# backlight.net
KiCad netlist of a schematic drawn in Altium Designer
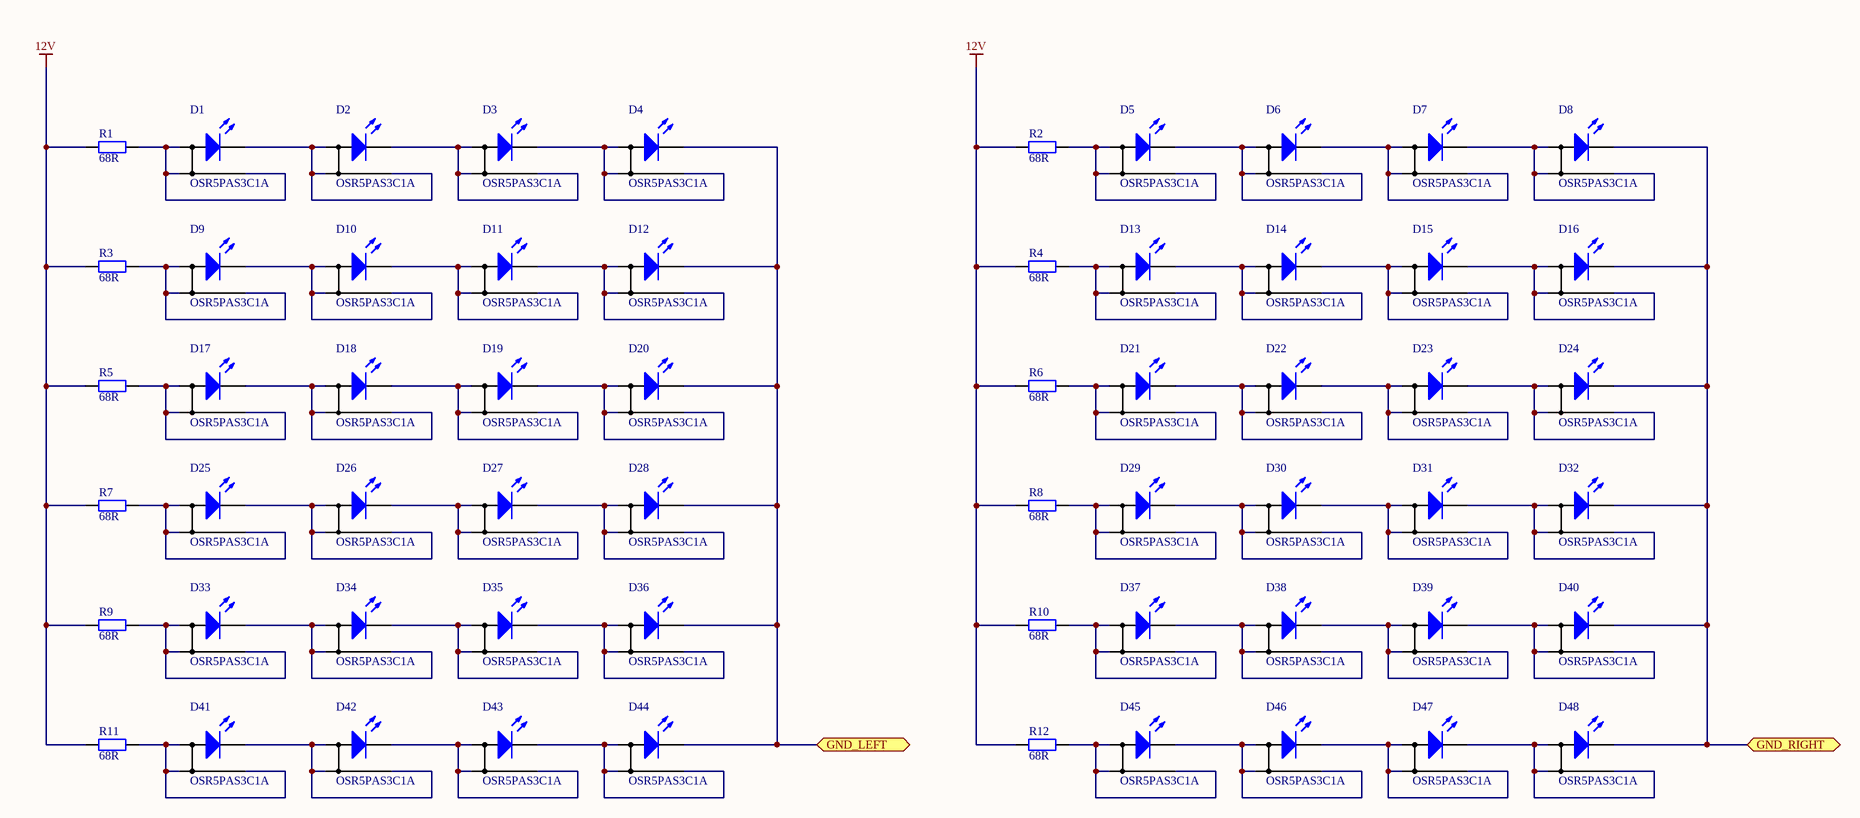
[diagram p0: backlight.SchDoc]

(export (version "E")
  (design (tool "Eeschema 10.0.6"))
  (components
    (comp (ref "D1")
      (value "DIO_LED_4pin_3528")
      (footprint "DIO_Optosupply_OSR5PAS3C1A")
      (description "High Luminous PLCC4 Power Top SMD LED")
      (fields (field (name "VALUE1") "OSR5PAS3C1A") (field (name "MANUFACTURER") "OptoSupply"))
      (libsource (lib "DSW_Lib") (part "DIO_LED_4pin_3528"))
    )
    (comp (ref "D2")
      (value "DIO_LED_4pin_3528")
      (footprint "DIO_Optosupply_OSR5PAS3C1A")
      (description "High Luminous PLCC4 Power Top SMD LED")
      (fields (field (name "VALUE1") "OSR5PAS3C1A") (field (name "MANUFACTURER") "OptoSupply"))
      (libsource (lib "DSW_Lib") (part "DIO_LED_4pin_3528"))
    )
    (comp (ref "D3")
      (value "DIO_LED_4pin_3528")
      (footprint "DIO_Optosupply_OSR5PAS3C1A")
      (description "High Luminous PLCC4 Power Top SMD LED")
      (fields (field (name "VALUE1") "OSR5PAS3C1A") (field (name "MANUFACTURER") "OptoSupply"))
      (libsource (lib "DSW_Lib") (part "DIO_LED_4pin_3528"))
    )
    (comp (ref "D4")
      (value "DIO_LED_4pin_3528")
      (footprint "DIO_Optosupply_OSR5PAS3C1A")
      (description "High Luminous PLCC4 Power Top SMD LED")
      (fields (field (name "VALUE1") "OSR5PAS3C1A") (field (name "MANUFACTURER") "OptoSupply"))
      (libsource (lib "DSW_Lib") (part "DIO_LED_4pin_3528"))
    )
    (comp (ref "D5")
      (value "DIO_LED_4pin_3528")
      (footprint "DIO_Optosupply_OSR5PAS3C1A")
      (description "High Luminous PLCC4 Power Top SMD LED")
      (fields (field (name "VALUE1") "OSR5PAS3C1A") (field (name "MANUFACTURER") "OptoSupply"))
      (libsource (lib "DSW_Lib") (part "DIO_LED_4pin_3528"))
    )
    (comp (ref "D6")
      (value "DIO_LED_4pin_3528")
      (footprint "DIO_Optosupply_OSR5PAS3C1A")
      (description "High Luminous PLCC4 Power Top SMD LED")
      (fields (field (name "VALUE1") "OSR5PAS3C1A") (field (name "MANUFACTURER") "OptoSupply"))
      (libsource (lib "DSW_Lib") (part "DIO_LED_4pin_3528"))
    )
    (comp (ref "D7")
      (value "DIO_LED_4pin_3528")
      (footprint "DIO_Optosupply_OSR5PAS3C1A")
      (description "High Luminous PLCC4 Power Top SMD LED")
      (fields (field (name "VALUE1") "OSR5PAS3C1A") (field (name "MANUFACTURER") "OptoSupply"))
      (libsource (lib "DSW_Lib") (part "DIO_LED_4pin_3528"))
    )
    (comp (ref "D8")
      (value "DIO_LED_4pin_3528")
      (footprint "DIO_Optosupply_OSR5PAS3C1A")
      (description "High Luminous PLCC4 Power Top SMD LED")
      (fields (field (name "VALUE1") "OSR5PAS3C1A") (field (name "MANUFACTURER") "OptoSupply"))
      (libsource (lib "DSW_Lib") (part "DIO_LED_4pin_3528"))
    )
    (comp (ref "D9")
      (value "DIO_LED_4pin_3528")
      (footprint "DIO_Optosupply_OSR5PAS3C1A")
      (description "High Luminous PLCC4 Power Top SMD LED")
      (fields (field (name "VALUE1") "OSR5PAS3C1A") (field (name "MANUFACTURER") "OptoSupply"))
      (libsource (lib "DSW_Lib") (part "DIO_LED_4pin_3528"))
    )
    (comp (ref "D10")
      (value "DIO_LED_4pin_3528")
      (footprint "DIO_Optosupply_OSR5PAS3C1A")
      (description "High Luminous PLCC4 Power Top SMD LED")
      (fields (field (name "VALUE1") "OSR5PAS3C1A") (field (name "MANUFACTURER") "OptoSupply"))
      (libsource (lib "DSW_Lib") (part "DIO_LED_4pin_3528"))
    )
    (comp (ref "D11")
      (value "DIO_LED_4pin_3528")
      (footprint "DIO_Optosupply_OSR5PAS3C1A")
      (description "High Luminous PLCC4 Power Top SMD LED")
      (fields (field (name "VALUE1") "OSR5PAS3C1A") (field (name "MANUFACTURER") "OptoSupply"))
      (libsource (lib "DSW_Lib") (part "DIO_LED_4pin_3528"))
    )
    (comp (ref "D12")
      (value "DIO_LED_4pin_3528")
      (footprint "DIO_Optosupply_OSR5PAS3C1A")
      (description "High Luminous PLCC4 Power Top SMD LED")
      (fields (field (name "VALUE1") "OSR5PAS3C1A") (field (name "MANUFACTURER") "OptoSupply"))
      (libsource (lib "DSW_Lib") (part "DIO_LED_4pin_3528"))
    )
    (comp (ref "D13")
      (value "DIO_LED_4pin_3528")
      (footprint "DIO_Optosupply_OSR5PAS3C1A")
      (description "High Luminous PLCC4 Power Top SMD LED")
      (fields (field (name "VALUE1") "OSR5PAS3C1A") (field (name "MANUFACTURER") "OptoSupply"))
      (libsource (lib "DSW_Lib") (part "DIO_LED_4pin_3528"))
    )
    (comp (ref "D14")
      (value "DIO_LED_4pin_3528")
      (footprint "DIO_Optosupply_OSR5PAS3C1A")
      (description "High Luminous PLCC4 Power Top SMD LED")
      (fields (field (name "VALUE1") "OSR5PAS3C1A") (field (name "MANUFACTURER") "OptoSupply"))
      (libsource (lib "DSW_Lib") (part "DIO_LED_4pin_3528"))
    )
    (comp (ref "D15")
      (value "DIO_LED_4pin_3528")
      (footprint "DIO_Optosupply_OSR5PAS3C1A")
      (description "High Luminous PLCC4 Power Top SMD LED")
      (fields (field (name "VALUE1") "OSR5PAS3C1A") (field (name "MANUFACTURER") "OptoSupply"))
      (libsource (lib "DSW_Lib") (part "DIO_LED_4pin_3528"))
    )
    (comp (ref "D16")
      (value "DIO_LED_4pin_3528")
      (footprint "DIO_Optosupply_OSR5PAS3C1A")
      (description "High Luminous PLCC4 Power Top SMD LED")
      (fields (field (name "VALUE1") "OSR5PAS3C1A") (field (name "MANUFACTURER") "OptoSupply"))
      (libsource (lib "DSW_Lib") (part "DIO_LED_4pin_3528"))
    )
    (comp (ref "D17")
      (value "DIO_LED_4pin_3528")
      (footprint "DIO_Optosupply_OSR5PAS3C1A")
      (description "High Luminous PLCC4 Power Top SMD LED")
      (fields (field (name "VALUE1") "OSR5PAS3C1A") (field (name "MANUFACTURER") "OptoSupply"))
      (libsource (lib "DSW_Lib") (part "DIO_LED_4pin_3528"))
    )
    (comp (ref "D18")
      (value "DIO_LED_4pin_3528")
      (footprint "DIO_Optosupply_OSR5PAS3C1A")
      (description "High Luminous PLCC4 Power Top SMD LED")
      (fields (field (name "VALUE1") "OSR5PAS3C1A") (field (name "MANUFACTURER") "OptoSupply"))
      (libsource (lib "DSW_Lib") (part "DIO_LED_4pin_3528"))
    )
    (comp (ref "D19")
      (value "DIO_LED_4pin_3528")
      (footprint "DIO_Optosupply_OSR5PAS3C1A")
      (description "High Luminous PLCC4 Power Top SMD LED")
      (fields (field (name "VALUE1") "OSR5PAS3C1A") (field (name "MANUFACTURER") "OptoSupply"))
      (libsource (lib "DSW_Lib") (part "DIO_LED_4pin_3528"))
    )
    (comp (ref "D20")
      (value "DIO_LED_4pin_3528")
      (footprint "DIO_Optosupply_OSR5PAS3C1A")
      (description "High Luminous PLCC4 Power Top SMD LED")
      (fields (field (name "VALUE1") "OSR5PAS3C1A") (field (name "MANUFACTURER") "OptoSupply"))
      (libsource (lib "DSW_Lib") (part "DIO_LED_4pin_3528"))
    )
    (comp (ref "D21")
      (value "DIO_LED_4pin_3528")
      (footprint "DIO_Optosupply_OSR5PAS3C1A")
      (description "High Luminous PLCC4 Power Top SMD LED")
      (fields (field (name "VALUE1") "OSR5PAS3C1A") (field (name "MANUFACTURER") "OptoSupply"))
      (libsource (lib "DSW_Lib") (part "DIO_LED_4pin_3528"))
    )
    (comp (ref "D22")
      (value "DIO_LED_4pin_3528")
      (footprint "DIO_Optosupply_OSR5PAS3C1A")
      (description "High Luminous PLCC4 Power Top SMD LED")
      (fields (field (name "VALUE1") "OSR5PAS3C1A") (field (name "MANUFACTURER") "OptoSupply"))
      (libsource (lib "DSW_Lib") (part "DIO_LED_4pin_3528"))
    )
    (comp (ref "D23")
      (value "DIO_LED_4pin_3528")
      (footprint "DIO_Optosupply_OSR5PAS3C1A")
      (description "High Luminous PLCC4 Power Top SMD LED")
      (fields (field (name "VALUE1") "OSR5PAS3C1A") (field (name "MANUFACTURER") "OptoSupply"))
      (libsource (lib "DSW_Lib") (part "DIO_LED_4pin_3528"))
    )
    (comp (ref "D24")
      (value "DIO_LED_4pin_3528")
      (footprint "DIO_Optosupply_OSR5PAS3C1A")
      (description "High Luminous PLCC4 Power Top SMD LED")
      (fields (field (name "VALUE1") "OSR5PAS3C1A") (field (name "MANUFACTURER") "OptoSupply"))
      (libsource (lib "DSW_Lib") (part "DIO_LED_4pin_3528"))
    )
    (comp (ref "D25")
      (value "DIO_LED_4pin_3528")
      (footprint "DIO_Optosupply_OSR5PAS3C1A")
      (description "High Luminous PLCC4 Power Top SMD LED")
      (fields (field (name "VALUE1") "OSR5PAS3C1A") (field (name "MANUFACTURER") "OptoSupply"))
      (libsource (lib "DSW_Lib") (part "DIO_LED_4pin_3528"))
    )
    (comp (ref "D26")
      (value "DIO_LED_4pin_3528")
      (footprint "DIO_Optosupply_OSR5PAS3C1A")
      (description "High Luminous PLCC4 Power Top SMD LED")
      (fields (field (name "VALUE1") "OSR5PAS3C1A") (field (name "MANUFACTURER") "OptoSupply"))
      (libsource (lib "DSW_Lib") (part "DIO_LED_4pin_3528"))
    )
    (comp (ref "D27")
      (value "DIO_LED_4pin_3528")
      (footprint "DIO_Optosupply_OSR5PAS3C1A")
      (description "High Luminous PLCC4 Power Top SMD LED")
      (fields (field (name "VALUE1") "OSR5PAS3C1A") (field (name "MANUFACTURER") "OptoSupply"))
      (libsource (lib "DSW_Lib") (part "DIO_LED_4pin_3528"))
    )
    (comp (ref "D28")
      (value "DIO_LED_4pin_3528")
      (footprint "DIO_Optosupply_OSR5PAS3C1A")
      (description "High Luminous PLCC4 Power Top SMD LED")
      (fields (field (name "VALUE1") "OSR5PAS3C1A") (field (name "MANUFACTURER") "OptoSupply"))
      (libsource (lib "DSW_Lib") (part "DIO_LED_4pin_3528"))
    )
    (comp (ref "D29")
      (value "DIO_LED_4pin_3528")
      (footprint "DIO_Optosupply_OSR5PAS3C1A")
      (description "High Luminous PLCC4 Power Top SMD LED")
      (fields (field (name "VALUE1") "OSR5PAS3C1A") (field (name "MANUFACTURER") "OptoSupply"))
      (libsource (lib "DSW_Lib") (part "DIO_LED_4pin_3528"))
    )
    (comp (ref "D30")
      (value "DIO_LED_4pin_3528")
      (footprint "DIO_Optosupply_OSR5PAS3C1A")
      (description "High Luminous PLCC4 Power Top SMD LED")
      (fields (field (name "VALUE1") "OSR5PAS3C1A") (field (name "MANUFACTURER") "OptoSupply"))
      (libsource (lib "DSW_Lib") (part "DIO_LED_4pin_3528"))
    )
    (comp (ref "D31")
      (value "DIO_LED_4pin_3528")
      (footprint "DIO_Optosupply_OSR5PAS3C1A")
      (description "High Luminous PLCC4 Power Top SMD LED")
      (fields (field (name "VALUE1") "OSR5PAS3C1A") (field (name "MANUFACTURER") "OptoSupply"))
      (libsource (lib "DSW_Lib") (part "DIO_LED_4pin_3528"))
    )
    (comp (ref "D32")
      (value "DIO_LED_4pin_3528")
      (footprint "DIO_Optosupply_OSR5PAS3C1A")
      (description "High Luminous PLCC4 Power Top SMD LED")
      (fields (field (name "VALUE1") "OSR5PAS3C1A") (field (name "MANUFACTURER") "OptoSupply"))
      (libsource (lib "DSW_Lib") (part "DIO_LED_4pin_3528"))
    )
    (comp (ref "D33")
      (value "DIO_LED_4pin_3528")
      (footprint "DIO_Optosupply_OSR5PAS3C1A")
      (description "High Luminous PLCC4 Power Top SMD LED")
      (fields (field (name "VALUE1") "OSR5PAS3C1A") (field (name "MANUFACTURER") "OptoSupply"))
      (libsource (lib "DSW_Lib") (part "DIO_LED_4pin_3528"))
    )
    (comp (ref "D34")
      (value "DIO_LED_4pin_3528")
      (footprint "DIO_Optosupply_OSR5PAS3C1A")
      (description "High Luminous PLCC4 Power Top SMD LED")
      (fields (field (name "VALUE1") "OSR5PAS3C1A") (field (name "MANUFACTURER") "OptoSupply"))
      (libsource (lib "DSW_Lib") (part "DIO_LED_4pin_3528"))
    )
    (comp (ref "D35")
      (value "DIO_LED_4pin_3528")
      (footprint "DIO_Optosupply_OSR5PAS3C1A")
      (description "High Luminous PLCC4 Power Top SMD LED")
      (fields (field (name "VALUE1") "OSR5PAS3C1A") (field (name "MANUFACTURER") "OptoSupply"))
      (libsource (lib "DSW_Lib") (part "DIO_LED_4pin_3528"))
    )
    (comp (ref "D36")
      (value "DIO_LED_4pin_3528")
      (footprint "DIO_Optosupply_OSR5PAS3C1A")
      (description "High Luminous PLCC4 Power Top SMD LED")
      (fields (field (name "VALUE1") "OSR5PAS3C1A") (field (name "MANUFACTURER") "OptoSupply"))
      (libsource (lib "DSW_Lib") (part "DIO_LED_4pin_3528"))
    )
    (comp (ref "D37")
      (value "DIO_LED_4pin_3528")
      (footprint "DIO_Optosupply_OSR5PAS3C1A")
      (description "High Luminous PLCC4 Power Top SMD LED")
      (fields (field (name "VALUE1") "OSR5PAS3C1A") (field (name "MANUFACTURER") "OptoSupply"))
      (libsource (lib "DSW_Lib") (part "DIO_LED_4pin_3528"))
    )
    (comp (ref "D38")
      (value "DIO_LED_4pin_3528")
      (footprint "DIO_Optosupply_OSR5PAS3C1A")
      (description "High Luminous PLCC4 Power Top SMD LED")
      (fields (field (name "VALUE1") "OSR5PAS3C1A") (field (name "MANUFACTURER") "OptoSupply"))
      (libsource (lib "DSW_Lib") (part "DIO_LED_4pin_3528"))
    )
    (comp (ref "D39")
      (value "DIO_LED_4pin_3528")
      (footprint "DIO_Optosupply_OSR5PAS3C1A")
      (description "High Luminous PLCC4 Power Top SMD LED")
      (fields (field (name "VALUE1") "OSR5PAS3C1A") (field (name "MANUFACTURER") "OptoSupply"))
      (libsource (lib "DSW_Lib") (part "DIO_LED_4pin_3528"))
    )
    (comp (ref "D40")
      (value "DIO_LED_4pin_3528")
      (footprint "DIO_Optosupply_OSR5PAS3C1A")
      (description "High Luminous PLCC4 Power Top SMD LED")
      (fields (field (name "VALUE1") "OSR5PAS3C1A") (field (name "MANUFACTURER") "OptoSupply"))
      (libsource (lib "DSW_Lib") (part "DIO_LED_4pin_3528"))
    )
    (comp (ref "D41")
      (value "DIO_LED_4pin_3528")
      (footprint "DIO_Optosupply_OSR5PAS3C1A")
      (description "High Luminous PLCC4 Power Top SMD LED")
      (fields (field (name "VALUE1") "OSR5PAS3C1A") (field (name "MANUFACTURER") "OptoSupply"))
      (libsource (lib "DSW_Lib") (part "DIO_LED_4pin_3528"))
    )
    (comp (ref "D42")
      (value "DIO_LED_4pin_3528")
      (footprint "DIO_Optosupply_OSR5PAS3C1A")
      (description "High Luminous PLCC4 Power Top SMD LED")
      (fields (field (name "VALUE1") "OSR5PAS3C1A") (field (name "MANUFACTURER") "OptoSupply"))
      (libsource (lib "DSW_Lib") (part "DIO_LED_4pin_3528"))
    )
    (comp (ref "D43")
      (value "DIO_LED_4pin_3528")
      (footprint "DIO_Optosupply_OSR5PAS3C1A")
      (description "High Luminous PLCC4 Power Top SMD LED")
      (fields (field (name "VALUE1") "OSR5PAS3C1A") (field (name "MANUFACTURER") "OptoSupply"))
      (libsource (lib "DSW_Lib") (part "DIO_LED_4pin_3528"))
    )
    (comp (ref "D44")
      (value "DIO_LED_4pin_3528")
      (footprint "DIO_Optosupply_OSR5PAS3C1A")
      (description "High Luminous PLCC4 Power Top SMD LED")
      (fields (field (name "VALUE1") "OSR5PAS3C1A") (field (name "MANUFACTURER") "OptoSupply"))
      (libsource (lib "DSW_Lib") (part "DIO_LED_4pin_3528"))
    )
    (comp (ref "D45")
      (value "DIO_LED_4pin_3528")
      (footprint "DIO_Optosupply_OSR5PAS3C1A")
      (description "High Luminous PLCC4 Power Top SMD LED")
      (fields (field (name "VALUE1") "OSR5PAS3C1A") (field (name "MANUFACTURER") "OptoSupply"))
      (libsource (lib "DSW_Lib") (part "DIO_LED_4pin_3528"))
    )
    (comp (ref "D46")
      (value "DIO_LED_4pin_3528")
      (footprint "DIO_Optosupply_OSR5PAS3C1A")
      (description "High Luminous PLCC4 Power Top SMD LED")
      (fields (field (name "VALUE1") "OSR5PAS3C1A") (field (name "MANUFACTURER") "OptoSupply"))
      (libsource (lib "DSW_Lib") (part "DIO_LED_4pin_3528"))
    )
    (comp (ref "D47")
      (value "DIO_LED_4pin_3528")
      (footprint "DIO_Optosupply_OSR5PAS3C1A")
      (description "High Luminous PLCC4 Power Top SMD LED")
      (fields (field (name "VALUE1") "OSR5PAS3C1A") (field (name "MANUFACTURER") "OptoSupply"))
      (libsource (lib "DSW_Lib") (part "DIO_LED_4pin_3528"))
    )
    (comp (ref "D48")
      (value "DIO_LED_4pin_3528")
      (footprint "DIO_Optosupply_OSR5PAS3C1A")
      (description "High Luminous PLCC4 Power Top SMD LED")
      (fields (field (name "VALUE1") "OSR5PAS3C1A") (field (name "MANUFACTURER") "OptoSupply"))
      (libsource (lib "DSW_Lib") (part "DIO_LED_4pin_3528"))
    )
    (comp (ref "R1")
      (value "RES")
      (footprint "RESC3116X65N")
      (description "1% SMT Resistor 1206")
      (fields (field (name "VALUE1") "68R") (field (name "MANUFACTURER") "Yageo"))
      (libsource (lib "DSW_Lib") (part "RES"))
    )
    (comp (ref "R2")
      (value "RES")
      (footprint "RESC3116X65N")
      (description "1% SMT Resistor 1206")
      (fields (field (name "VALUE1") "68R") (field (name "MANUFACTURER") "Yageo"))
      (libsource (lib "DSW_Lib") (part "RES"))
    )
    (comp (ref "R3")
      (value "RES")
      (footprint "RESC3116X65N")
      (description "1% SMT Resistor 1206")
      (fields (field (name "VALUE1") "68R") (field (name "MANUFACTURER") "Yageo"))
      (libsource (lib "DSW_Lib") (part "RES"))
    )
    (comp (ref "R4")
      (value "RES")
      (footprint "RESC3116X65N")
      (description "1% SMT Resistor 1206")
      (fields (field (name "VALUE1") "68R") (field (name "MANUFACTURER") "Yageo"))
      (libsource (lib "DSW_Lib") (part "RES"))
    )
    (comp (ref "R5")
      (value "RES")
      (footprint "RESC3116X65N")
      (description "1% SMT Resistor 1206")
      (fields (field (name "VALUE1") "68R") (field (name "MANUFACTURER") "Yageo"))
      (libsource (lib "DSW_Lib") (part "RES"))
    )
    (comp (ref "R6")
      (value "RES")
      (footprint "RESC3116X65N")
      (description "1% SMT Resistor 1206")
      (fields (field (name "VALUE1") "68R") (field (name "MANUFACTURER") "Yageo"))
      (libsource (lib "DSW_Lib") (part "RES"))
    )
    (comp (ref "R7")
      (value "RES")
      (footprint "RESC3116X65N")
      (description "1% SMT Resistor 1206")
      (fields (field (name "VALUE1") "68R") (field (name "MANUFACTURER") "Yageo"))
      (libsource (lib "DSW_Lib") (part "RES"))
    )
    (comp (ref "R8")
      (value "RES")
      (footprint "RESC3116X65N")
      (description "1% SMT Resistor 1206")
      (fields (field (name "VALUE1") "68R") (field (name "MANUFACTURER") "Yageo"))
      (libsource (lib "DSW_Lib") (part "RES"))
    )
    (comp (ref "R9")
      (value "RES")
      (footprint "RESC3116X65N")
      (description "1% SMT Resistor 1206")
      (fields (field (name "VALUE1") "68R") (field (name "MANUFACTURER") "Yageo"))
      (libsource (lib "DSW_Lib") (part "RES"))
    )
    (comp (ref "R10")
      (value "RES")
      (footprint "RESC3116X65N")
      (description "1% SMT Resistor 1206")
      (fields (field (name "VALUE1") "68R") (field (name "MANUFACTURER") "Yageo"))
      (libsource (lib "DSW_Lib") (part "RES"))
    )
    (comp (ref "R11")
      (value "RES")
      (footprint "RESC3116X65N")
      (description "1% SMT Resistor 1206")
      (fields (field (name "VALUE1") "68R") (field (name "MANUFACTURER") "Yageo"))
      (libsource (lib "DSW_Lib") (part "RES"))
    )
    (comp (ref "R12")
      (value "RES")
      (footprint "RESC3116X65N")
      (description "1% SMT Resistor 1206")
      (fields (field (name "VALUE1") "68R") (field (name "MANUFACTURER") "Yageo"))
      (libsource (lib "DSW_Lib") (part "RES"))
    )
  )
  (nets
    (net (code "1") (name "/GND_LEFT") (class "Default")
      (node (ref "D12") (pin "1") (pinfunction "K_1") (pintype "passive"))
      (node (ref "D20") (pin "1") (pinfunction "K_1") (pintype "passive"))
      (node (ref "D28") (pin "1") (pinfunction "K_1") (pintype "passive"))
      (node (ref "D36") (pin "1") (pinfunction "K_1") (pintype "passive"))
      (node (ref "D4") (pin "1") (pinfunction "K_1") (pintype "passive"))
      (node (ref "D44") (pin "1") (pinfunction "K_1") (pintype "passive"))
    )
    (net (code "2") (name "/GND_RIGHT") (class "Default")
      (node (ref "D16") (pin "1") (pinfunction "K_1") (pintype "passive"))
      (node (ref "D24") (pin "1") (pinfunction "K_1") (pintype "passive"))
      (node (ref "D32") (pin "1") (pinfunction "K_1") (pintype "passive"))
      (node (ref "D40") (pin "1") (pinfunction "K_1") (pintype "passive"))
      (node (ref "D48") (pin "1") (pinfunction "K_1") (pintype "passive"))
      (node (ref "D8") (pin "1") (pinfunction "K_1") (pintype "passive"))
    )
    (net (code "3") (name "12V") (class "Default")
      (node (ref "R1") (pin "1") (pinfunction "1_1") (pintype "passive"))
      (node (ref "R10") (pin "1") (pinfunction "1_1") (pintype "passive"))
      (node (ref "R11") (pin "1") (pinfunction "1_1") (pintype "passive"))
      (node (ref "R12") (pin "1") (pinfunction "1_1") (pintype "passive"))
      (node (ref "R2") (pin "1") (pinfunction "1_1") (pintype "passive"))
      (node (ref "R3") (pin "1") (pinfunction "1_1") (pintype "passive"))
      (node (ref "R4") (pin "1") (pinfunction "1_1") (pintype "passive"))
      (node (ref "R5") (pin "1") (pinfunction "1_1") (pintype "passive"))
      (node (ref "R6") (pin "1") (pinfunction "1_1") (pintype "passive"))
      (node (ref "R7") (pin "1") (pinfunction "1_1") (pintype "passive"))
      (node (ref "R8") (pin "1") (pinfunction "1_1") (pintype "passive"))
      (node (ref "R9") (pin "1") (pinfunction "1_1") (pintype "passive"))
    )
    (net (code "4") (name "Net-(D1-A)") (class "Default")
      (node (ref "D1") (pin "2") (pinfunction "2_2") (pintype "passive"))
      (node (ref "D1") (pin "3") (pinfunction "A_3") (pintype "passive"))
      (node (ref "D1") (pin "4") (pinfunction "4_4") (pintype "passive"))
      (node (ref "R1") (pin "2") (pinfunction "2_2") (pintype "passive"))
    )
    (net (code "5") (name "Net-(D1-K)") (class "Default")
      (node (ref "D1") (pin "1") (pinfunction "K_1") (pintype "passive"))
      (node (ref "D2") (pin "2") (pinfunction "2_2") (pintype "passive"))
      (node (ref "D2") (pin "3") (pinfunction "A_3") (pintype "passive"))
      (node (ref "D2") (pin "4") (pinfunction "4_4") (pintype "passive"))
    )
    (net (code "6") (name "Net-(D2-K)") (class "Default")
      (node (ref "D2") (pin "1") (pinfunction "K_1") (pintype "passive"))
      (node (ref "D3") (pin "2") (pinfunction "2_2") (pintype "passive"))
      (node (ref "D3") (pin "3") (pinfunction "A_3") (pintype "passive"))
      (node (ref "D3") (pin "4") (pinfunction "4_4") (pintype "passive"))
    )
    (net (code "7") (name "Net-(D3-K)") (class "Default")
      (node (ref "D3") (pin "1") (pinfunction "K_1") (pintype "passive"))
      (node (ref "D4") (pin "2") (pinfunction "2_2") (pintype "passive"))
      (node (ref "D4") (pin "3") (pinfunction "A_3") (pintype "passive"))
      (node (ref "D4") (pin "4") (pinfunction "4_4") (pintype "passive"))
    )
    (net (code "8") (name "Net-(D5-A)") (class "Default")
      (node (ref "D5") (pin "2") (pinfunction "2_2") (pintype "passive"))
      (node (ref "D5") (pin "3") (pinfunction "A_3") (pintype "passive"))
      (node (ref "D5") (pin "4") (pinfunction "4_4") (pintype "passive"))
      (node (ref "R2") (pin "2") (pinfunction "2_2") (pintype "passive"))
    )
    (net (code "9") (name "Net-(D5-K)") (class "Default")
      (node (ref "D5") (pin "1") (pinfunction "K_1") (pintype "passive"))
      (node (ref "D6") (pin "2") (pinfunction "2_2") (pintype "passive"))
      (node (ref "D6") (pin "3") (pinfunction "A_3") (pintype "passive"))
      (node (ref "D6") (pin "4") (pinfunction "4_4") (pintype "passive"))
    )
    (net (code "10") (name "Net-(D6-K)") (class "Default")
      (node (ref "D6") (pin "1") (pinfunction "K_1") (pintype "passive"))
      (node (ref "D7") (pin "2") (pinfunction "2_2") (pintype "passive"))
      (node (ref "D7") (pin "3") (pinfunction "A_3") (pintype "passive"))
      (node (ref "D7") (pin "4") (pinfunction "4_4") (pintype "passive"))
    )
    (net (code "11") (name "Net-(D7-K)") (class "Default")
      (node (ref "D7") (pin "1") (pinfunction "K_1") (pintype "passive"))
      (node (ref "D8") (pin "2") (pinfunction "2_2") (pintype "passive"))
      (node (ref "D8") (pin "3") (pinfunction "A_3") (pintype "passive"))
      (node (ref "D8") (pin "4") (pinfunction "4_4") (pintype "passive"))
    )
    (net (code "12") (name "Net-(D9-A)") (class "Default")
      (node (ref "D9") (pin "2") (pinfunction "2_2") (pintype "passive"))
      (node (ref "D9") (pin "3") (pinfunction "A_3") (pintype "passive"))
      (node (ref "D9") (pin "4") (pinfunction "4_4") (pintype "passive"))
      (node (ref "R3") (pin "2") (pinfunction "2_2") (pintype "passive"))
    )
    (net (code "13") (name "Net-(D10-A)") (class "Default")
      (node (ref "D10") (pin "2") (pinfunction "2_2") (pintype "passive"))
      (node (ref "D10") (pin "3") (pinfunction "A_3") (pintype "passive"))
      (node (ref "D10") (pin "4") (pinfunction "4_4") (pintype "passive"))
      (node (ref "D9") (pin "1") (pinfunction "K_1") (pintype "passive"))
    )
    (net (code "14") (name "Net-(D10-K)") (class "Default")
      (node (ref "D10") (pin "1") (pinfunction "K_1") (pintype "passive"))
      (node (ref "D11") (pin "2") (pinfunction "2_2") (pintype "passive"))
      (node (ref "D11") (pin "3") (pinfunction "A_3") (pintype "passive"))
      (node (ref "D11") (pin "4") (pinfunction "4_4") (pintype "passive"))
    )
    (net (code "15") (name "Net-(D11-K)") (class "Default")
      (node (ref "D11") (pin "1") (pinfunction "K_1") (pintype "passive"))
      (node (ref "D12") (pin "2") (pinfunction "2_2") (pintype "passive"))
      (node (ref "D12") (pin "3") (pinfunction "A_3") (pintype "passive"))
      (node (ref "D12") (pin "4") (pinfunction "4_4") (pintype "passive"))
    )
    (net (code "16") (name "Net-(D13-A)") (class "Default")
      (node (ref "D13") (pin "2") (pinfunction "2_2") (pintype "passive"))
      (node (ref "D13") (pin "3") (pinfunction "A_3") (pintype "passive"))
      (node (ref "D13") (pin "4") (pinfunction "4_4") (pintype "passive"))
      (node (ref "R4") (pin "2") (pinfunction "2_2") (pintype "passive"))
    )
    (net (code "17") (name "Net-(D13-K)") (class "Default")
      (node (ref "D13") (pin "1") (pinfunction "K_1") (pintype "passive"))
      (node (ref "D14") (pin "2") (pinfunction "2_2") (pintype "passive"))
      (node (ref "D14") (pin "3") (pinfunction "A_3") (pintype "passive"))
      (node (ref "D14") (pin "4") (pinfunction "4_4") (pintype "passive"))
    )
    (net (code "18") (name "Net-(D14-K)") (class "Default")
      (node (ref "D14") (pin "1") (pinfunction "K_1") (pintype "passive"))
      (node (ref "D15") (pin "2") (pinfunction "2_2") (pintype "passive"))
      (node (ref "D15") (pin "3") (pinfunction "A_3") (pintype "passive"))
      (node (ref "D15") (pin "4") (pinfunction "4_4") (pintype "passive"))
    )
    (net (code "19") (name "Net-(D15-K)") (class "Default")
      (node (ref "D15") (pin "1") (pinfunction "K_1") (pintype "passive"))
      (node (ref "D16") (pin "2") (pinfunction "2_2") (pintype "passive"))
      (node (ref "D16") (pin "3") (pinfunction "A_3") (pintype "passive"))
      (node (ref "D16") (pin "4") (pinfunction "4_4") (pintype "passive"))
    )
    (net (code "20") (name "Net-(D17-A)") (class "Default")
      (node (ref "D17") (pin "2") (pinfunction "2_2") (pintype "passive"))
      (node (ref "D17") (pin "3") (pinfunction "A_3") (pintype "passive"))
      (node (ref "D17") (pin "4") (pinfunction "4_4") (pintype "passive"))
      (node (ref "R5") (pin "2") (pinfunction "2_2") (pintype "passive"))
    )
    (net (code "21") (name "Net-(D17-K)") (class "Default")
      (node (ref "D17") (pin "1") (pinfunction "K_1") (pintype "passive"))
      (node (ref "D18") (pin "2") (pinfunction "2_2") (pintype "passive"))
      (node (ref "D18") (pin "3") (pinfunction "A_3") (pintype "passive"))
      (node (ref "D18") (pin "4") (pinfunction "4_4") (pintype "passive"))
    )
    (net (code "22") (name "Net-(D18-K)") (class "Default")
      (node (ref "D18") (pin "1") (pinfunction "K_1") (pintype "passive"))
      (node (ref "D19") (pin "2") (pinfunction "2_2") (pintype "passive"))
      (node (ref "D19") (pin "3") (pinfunction "A_3") (pintype "passive"))
      (node (ref "D19") (pin "4") (pinfunction "4_4") (pintype "passive"))
    )
    (net (code "23") (name "Net-(D19-K)") (class "Default")
      (node (ref "D19") (pin "1") (pinfunction "K_1") (pintype "passive"))
      (node (ref "D20") (pin "2") (pinfunction "2_2") (pintype "passive"))
      (node (ref "D20") (pin "3") (pinfunction "A_3") (pintype "passive"))
      (node (ref "D20") (pin "4") (pinfunction "4_4") (pintype "passive"))
    )
    (net (code "24") (name "Net-(D21-A)") (class "Default")
      (node (ref "D21") (pin "2") (pinfunction "2_2") (pintype "passive"))
      (node (ref "D21") (pin "3") (pinfunction "A_3") (pintype "passive"))
      (node (ref "D21") (pin "4") (pinfunction "4_4") (pintype "passive"))
      (node (ref "R6") (pin "2") (pinfunction "2_2") (pintype "passive"))
    )
    (net (code "25") (name "Net-(D21-K)") (class "Default")
      (node (ref "D21") (pin "1") (pinfunction "K_1") (pintype "passive"))
      (node (ref "D22") (pin "2") (pinfunction "2_2") (pintype "passive"))
      (node (ref "D22") (pin "3") (pinfunction "A_3") (pintype "passive"))
      (node (ref "D22") (pin "4") (pinfunction "4_4") (pintype "passive"))
    )
    (net (code "26") (name "Net-(D22-K)") (class "Default")
      (node (ref "D22") (pin "1") (pinfunction "K_1") (pintype "passive"))
      (node (ref "D23") (pin "2") (pinfunction "2_2") (pintype "passive"))
      (node (ref "D23") (pin "3") (pinfunction "A_3") (pintype "passive"))
      (node (ref "D23") (pin "4") (pinfunction "4_4") (pintype "passive"))
    )
    (net (code "27") (name "Net-(D23-K)") (class "Default")
      (node (ref "D23") (pin "1") (pinfunction "K_1") (pintype "passive"))
      (node (ref "D24") (pin "2") (pinfunction "2_2") (pintype "passive"))
      (node (ref "D24") (pin "3") (pinfunction "A_3") (pintype "passive"))
      (node (ref "D24") (pin "4") (pinfunction "4_4") (pintype "passive"))
    )
    (net (code "28") (name "Net-(D25-A)") (class "Default")
      (node (ref "D25") (pin "2") (pinfunction "2_2") (pintype "passive"))
      (node (ref "D25") (pin "3") (pinfunction "A_3") (pintype "passive"))
      (node (ref "D25") (pin "4") (pinfunction "4_4") (pintype "passive"))
      (node (ref "R7") (pin "2") (pinfunction "2_2") (pintype "passive"))
    )
    (net (code "29") (name "Net-(D25-K)") (class "Default")
      (node (ref "D25") (pin "1") (pinfunction "K_1") (pintype "passive"))
      (node (ref "D26") (pin "2") (pinfunction "2_2") (pintype "passive"))
      (node (ref "D26") (pin "3") (pinfunction "A_3") (pintype "passive"))
      (node (ref "D26") (pin "4") (pinfunction "4_4") (pintype "passive"))
    )
    (net (code "30") (name "Net-(D26-K)") (class "Default")
      (node (ref "D26") (pin "1") (pinfunction "K_1") (pintype "passive"))
      (node (ref "D27") (pin "2") (pinfunction "2_2") (pintype "passive"))
      (node (ref "D27") (pin "3") (pinfunction "A_3") (pintype "passive"))
      (node (ref "D27") (pin "4") (pinfunction "4_4") (pintype "passive"))
    )
    (net (code "31") (name "Net-(D27-K)") (class "Default")
      (node (ref "D27") (pin "1") (pinfunction "K_1") (pintype "passive"))
      (node (ref "D28") (pin "2") (pinfunction "2_2") (pintype "passive"))
      (node (ref "D28") (pin "3") (pinfunction "A_3") (pintype "passive"))
      (node (ref "D28") (pin "4") (pinfunction "4_4") (pintype "passive"))
    )
    (net (code "32") (name "Net-(D29-A)") (class "Default")
      (node (ref "D29") (pin "2") (pinfunction "2_2") (pintype "passive"))
      (node (ref "D29") (pin "3") (pinfunction "A_3") (pintype "passive"))
      (node (ref "D29") (pin "4") (pinfunction "4_4") (pintype "passive"))
      (node (ref "R8") (pin "2") (pinfunction "2_2") (pintype "passive"))
    )
    (net (code "33") (name "Net-(D29-K)") (class "Default")
      (node (ref "D29") (pin "1") (pinfunction "K_1") (pintype "passive"))
      (node (ref "D30") (pin "2") (pinfunction "2_2") (pintype "passive"))
      (node (ref "D30") (pin "3") (pinfunction "A_3") (pintype "passive"))
      (node (ref "D30") (pin "4") (pinfunction "4_4") (pintype "passive"))
    )
    (net (code "34") (name "Net-(D30-K)") (class "Default")
      (node (ref "D30") (pin "1") (pinfunction "K_1") (pintype "passive"))
      (node (ref "D31") (pin "2") (pinfunction "2_2") (pintype "passive"))
      (node (ref "D31") (pin "3") (pinfunction "A_3") (pintype "passive"))
      (node (ref "D31") (pin "4") (pinfunction "4_4") (pintype "passive"))
    )
    (net (code "35") (name "Net-(D31-K)") (class "Default")
      (node (ref "D31") (pin "1") (pinfunction "K_1") (pintype "passive"))
      (node (ref "D32") (pin "2") (pinfunction "2_2") (pintype "passive"))
      (node (ref "D32") (pin "3") (pinfunction "A_3") (pintype "passive"))
      (node (ref "D32") (pin "4") (pinfunction "4_4") (pintype "passive"))
    )
    (net (code "36") (name "Net-(D33-A)") (class "Default")
      (node (ref "D33") (pin "2") (pinfunction "2_2") (pintype "passive"))
      (node (ref "D33") (pin "3") (pinfunction "A_3") (pintype "passive"))
      (node (ref "D33") (pin "4") (pinfunction "4_4") (pintype "passive"))
      (node (ref "R9") (pin "2") (pinfunction "2_2") (pintype "passive"))
    )
    (net (code "37") (name "Net-(D33-K)") (class "Default")
      (node (ref "D33") (pin "1") (pinfunction "K_1") (pintype "passive"))
      (node (ref "D34") (pin "2") (pinfunction "2_2") (pintype "passive"))
      (node (ref "D34") (pin "3") (pinfunction "A_3") (pintype "passive"))
      (node (ref "D34") (pin "4") (pinfunction "4_4") (pintype "passive"))
    )
    (net (code "38") (name "Net-(D34-K)") (class "Default")
      (node (ref "D34") (pin "1") (pinfunction "K_1") (pintype "passive"))
      (node (ref "D35") (pin "2") (pinfunction "2_2") (pintype "passive"))
      (node (ref "D35") (pin "3") (pinfunction "A_3") (pintype "passive"))
      (node (ref "D35") (pin "4") (pinfunction "4_4") (pintype "passive"))
    )
    (net (code "39") (name "Net-(D35-K)") (class "Default")
      (node (ref "D35") (pin "1") (pinfunction "K_1") (pintype "passive"))
      (node (ref "D36") (pin "2") (pinfunction "2_2") (pintype "passive"))
      (node (ref "D36") (pin "3") (pinfunction "A_3") (pintype "passive"))
      (node (ref "D36") (pin "4") (pinfunction "4_4") (pintype "passive"))
    )
    (net (code "40") (name "Net-(D37-A)") (class "Default")
      (node (ref "D37") (pin "2") (pinfunction "2_2") (pintype "passive"))
      (node (ref "D37") (pin "3") (pinfunction "A_3") (pintype "passive"))
      (node (ref "D37") (pin "4") (pinfunction "4_4") (pintype "passive"))
      (node (ref "R10") (pin "2") (pinfunction "2_2") (pintype "passive"))
    )
    (net (code "41") (name "Net-(D37-K)") (class "Default")
      (node (ref "D37") (pin "1") (pinfunction "K_1") (pintype "passive"))
      (node (ref "D38") (pin "2") (pinfunction "2_2") (pintype "passive"))
      (node (ref "D38") (pin "3") (pinfunction "A_3") (pintype "passive"))
      (node (ref "D38") (pin "4") (pinfunction "4_4") (pintype "passive"))
    )
    (net (code "42") (name "Net-(D38-K)") (class "Default")
      (node (ref "D38") (pin "1") (pinfunction "K_1") (pintype "passive"))
      (node (ref "D39") (pin "2") (pinfunction "2_2") (pintype "passive"))
      (node (ref "D39") (pin "3") (pinfunction "A_3") (pintype "passive"))
      (node (ref "D39") (pin "4") (pinfunction "4_4") (pintype "passive"))
    )
    (net (code "43") (name "Net-(D39-K)") (class "Default")
      (node (ref "D39") (pin "1") (pinfunction "K_1") (pintype "passive"))
      (node (ref "D40") (pin "2") (pinfunction "2_2") (pintype "passive"))
      (node (ref "D40") (pin "3") (pinfunction "A_3") (pintype "passive"))
      (node (ref "D40") (pin "4") (pinfunction "4_4") (pintype "passive"))
    )
    (net (code "44") (name "Net-(D41-A)") (class "Default")
      (node (ref "D41") (pin "2") (pinfunction "2_2") (pintype "passive"))
      (node (ref "D41") (pin "3") (pinfunction "A_3") (pintype "passive"))
      (node (ref "D41") (pin "4") (pinfunction "4_4") (pintype "passive"))
      (node (ref "R11") (pin "2") (pinfunction "2_2") (pintype "passive"))
    )
    (net (code "45") (name "Net-(D41-K)") (class "Default")
      (node (ref "D41") (pin "1") (pinfunction "K_1") (pintype "passive"))
      (node (ref "D42") (pin "2") (pinfunction "2_2") (pintype "passive"))
      (node (ref "D42") (pin "3") (pinfunction "A_3") (pintype "passive"))
      (node (ref "D42") (pin "4") (pinfunction "4_4") (pintype "passive"))
    )
    (net (code "46") (name "Net-(D42-K)") (class "Default")
      (node (ref "D42") (pin "1") (pinfunction "K_1") (pintype "passive"))
      (node (ref "D43") (pin "2") (pinfunction "2_2") (pintype "passive"))
      (node (ref "D43") (pin "3") (pinfunction "A_3") (pintype "passive"))
      (node (ref "D43") (pin "4") (pinfunction "4_4") (pintype "passive"))
    )
    (net (code "47") (name "Net-(D43-K)") (class "Default")
      (node (ref "D43") (pin "1") (pinfunction "K_1") (pintype "passive"))
      (node (ref "D44") (pin "2") (pinfunction "2_2") (pintype "passive"))
      (node (ref "D44") (pin "3") (pinfunction "A_3") (pintype "passive"))
      (node (ref "D44") (pin "4") (pinfunction "4_4") (pintype "passive"))
    )
    (net (code "48") (name "Net-(D45-A)") (class "Default")
      (node (ref "D45") (pin "2") (pinfunction "2_2") (pintype "passive"))
      (node (ref "D45") (pin "3") (pinfunction "A_3") (pintype "passive"))
      (node (ref "D45") (pin "4") (pinfunction "4_4") (pintype "passive"))
      (node (ref "R12") (pin "2") (pinfunction "2_2") (pintype "passive"))
    )
    (net (code "49") (name "Net-(D45-K)") (class "Default")
      (node (ref "D45") (pin "1") (pinfunction "K_1") (pintype "passive"))
      (node (ref "D46") (pin "2") (pinfunction "2_2") (pintype "passive"))
      (node (ref "D46") (pin "3") (pinfunction "A_3") (pintype "passive"))
      (node (ref "D46") (pin "4") (pinfunction "4_4") (pintype "passive"))
    )
    (net (code "50") (name "Net-(D46-K)") (class "Default")
      (node (ref "D46") (pin "1") (pinfunction "K_1") (pintype "passive"))
      (node (ref "D47") (pin "2") (pinfunction "2_2") (pintype "passive"))
      (node (ref "D47") (pin "3") (pinfunction "A_3") (pintype "passive"))
      (node (ref "D47") (pin "4") (pinfunction "4_4") (pintype "passive"))
    )
    (net (code "51") (name "Net-(D47-K)") (class "Default")
      (node (ref "D47") (pin "1") (pinfunction "K_1") (pintype "passive"))
      (node (ref "D48") (pin "2") (pinfunction "2_2") (pintype "passive"))
      (node (ref "D48") (pin "3") (pinfunction "A_3") (pintype "passive"))
      (node (ref "D48") (pin "4") (pinfunction "4_4") (pintype "passive"))
    )
  )
)
